# DM1097_HUB.net
KiCad netlist of a schematic drawn in Altium Designer
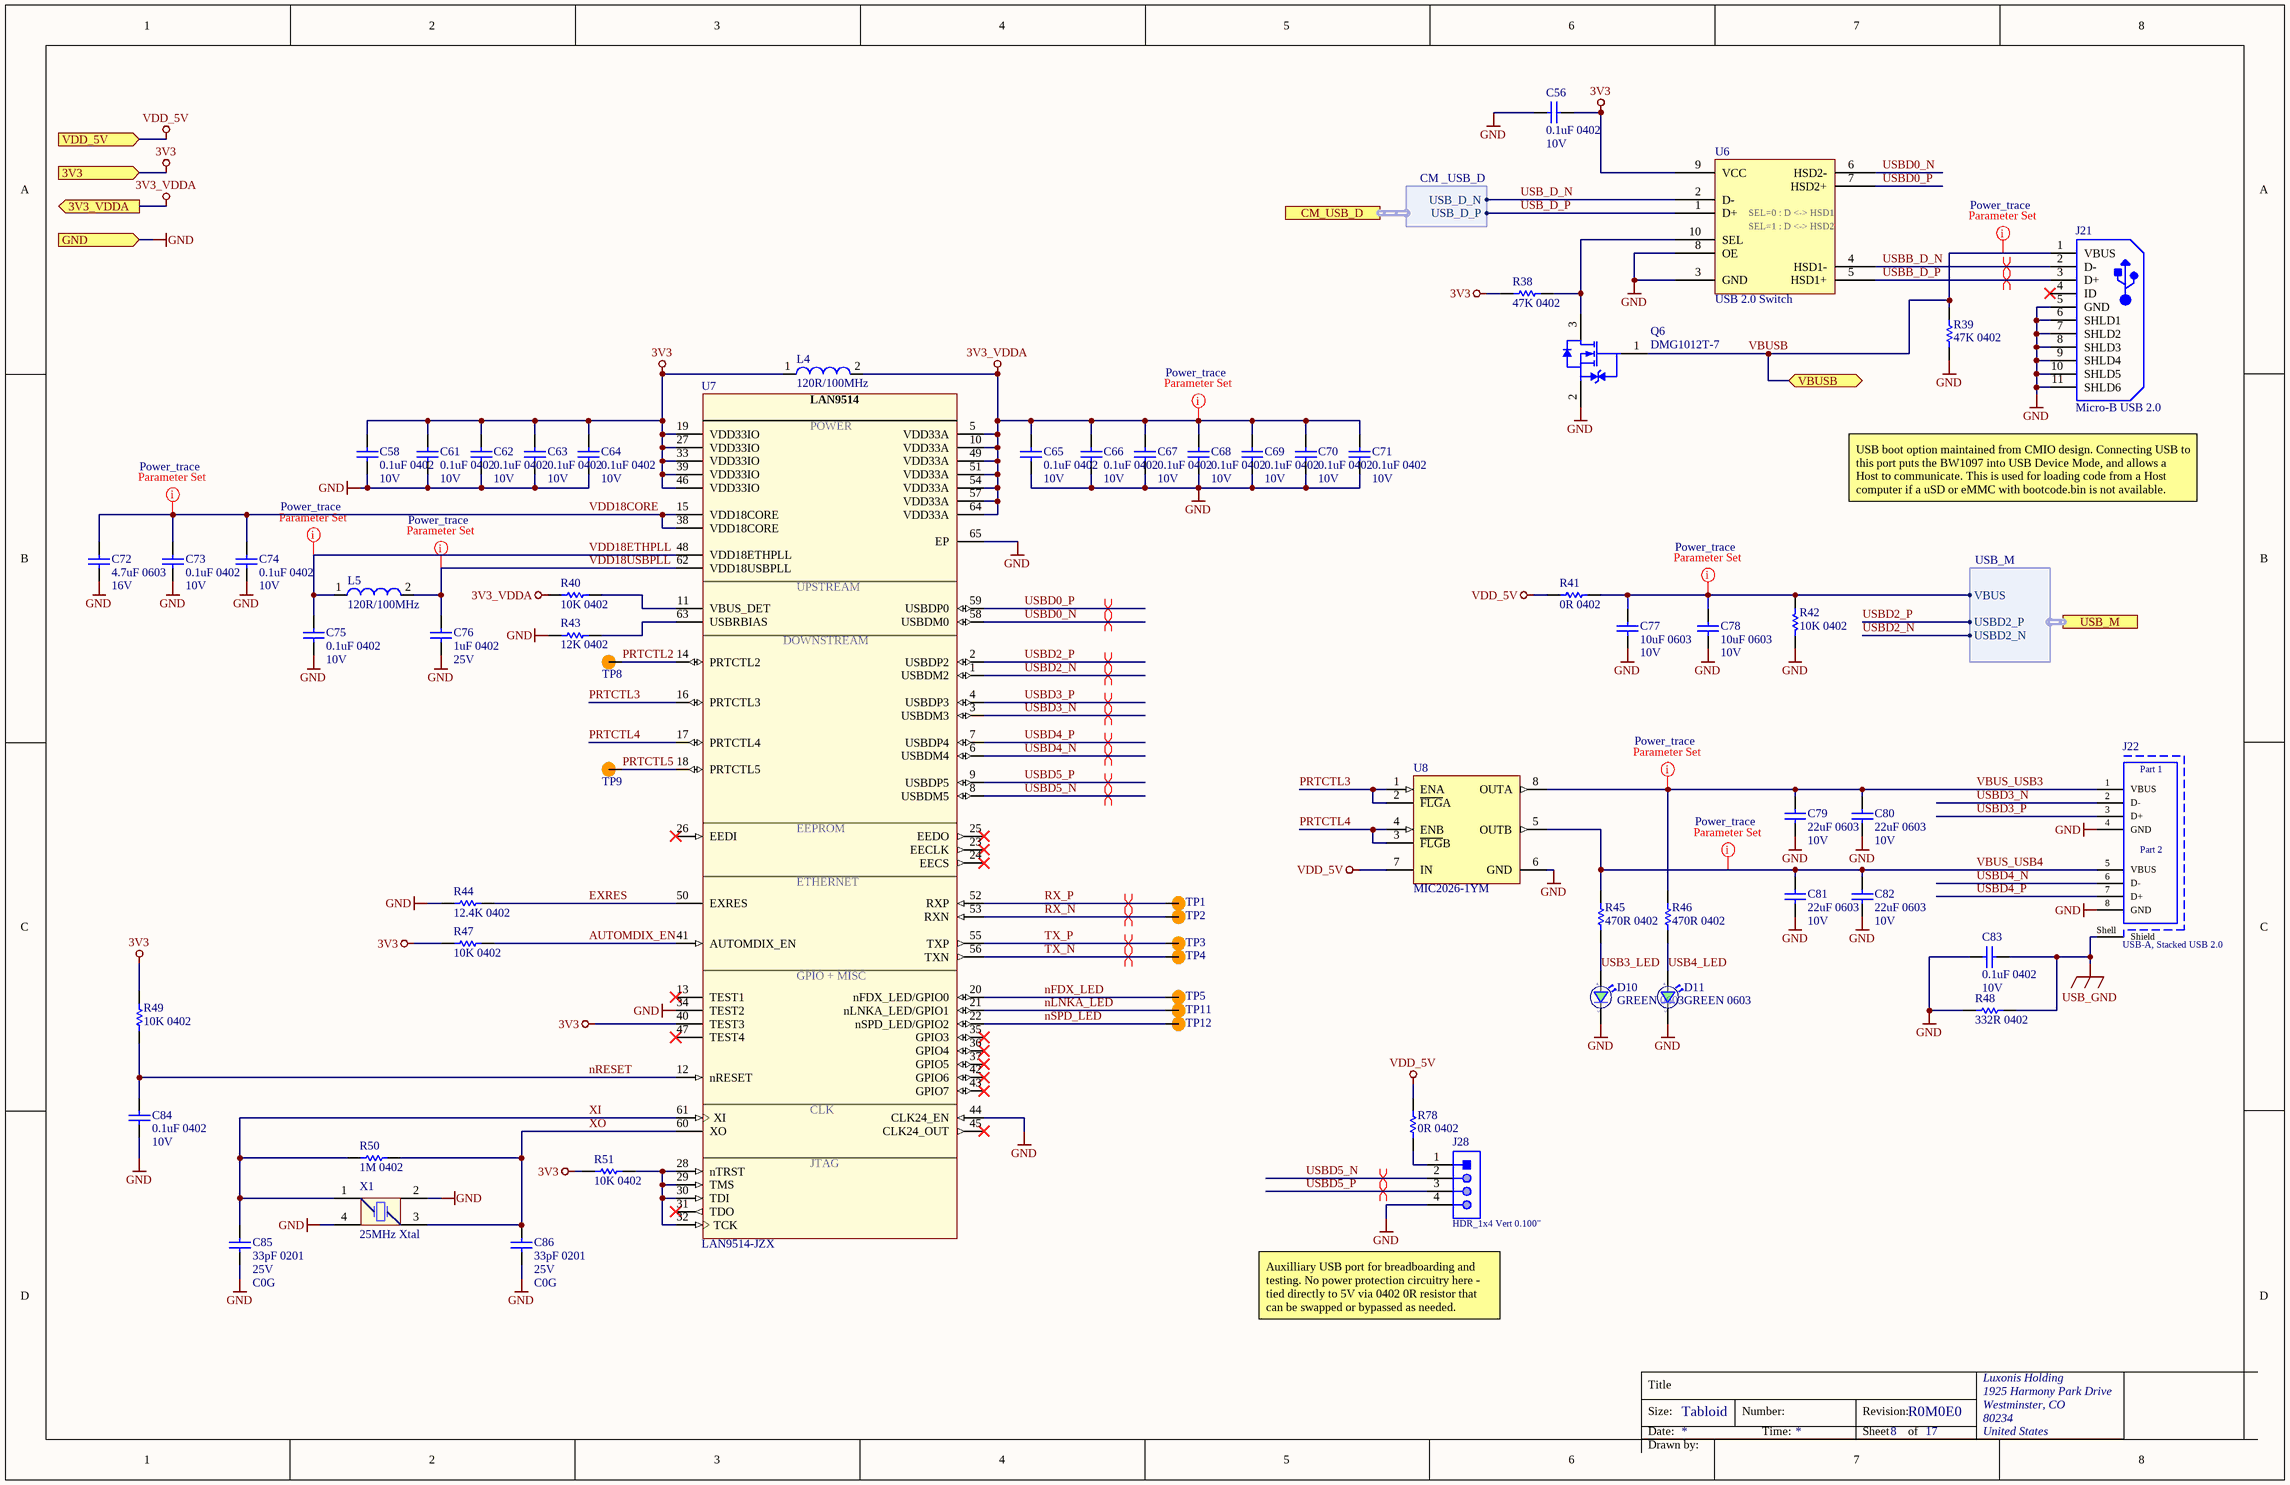
[diagram p0: DM1097_HUB.SchDoc]

(export (version "E")
  (design (tool "Eeschema 10.0.6"))
  (components
    (comp (ref "C56")
      (value "0.1uF 0402")
      (footprint "CAP_Altium_Vault_Generic:CAPC0402(1005)70_N")
      (description "CAP CER 0.1UF 10V X7R 0402 5%")
      (fields (field (name "TOLERANCE") "5%") (field (name "VOLTAGE RATING") "10V"))
      (libsource (lib "LuxonisMaster") (part "GRM155R71A104JA01D"))
    )
    (comp (ref "C58")
      (value "0.1uF 0402")
      (footprint "CAP_Altium_Vault_Generic:CAPC0402(1005)70_N")
      (description "CAP CER 0.1UF 10V X7R 0402 5%")
      (fields (field (name "TOLERANCE") "5%") (field (name "VOLTAGE RATING") "10V"))
      (libsource (lib "LuxonisMaster") (part "GRM155R71A104JA01D"))
    )
    (comp (ref "C61")
      (value "0.1uF 0402")
      (footprint "CAP_Altium_Vault_Generic:CAPC0402(1005)70_N")
      (description "CAP CER 0.1UF 10V X7R 0402 5%")
      (fields (field (name "TOLERANCE") "5%") (field (name "VOLTAGE RATING") "10V"))
      (libsource (lib "LuxonisMaster") (part "GRM155R71A104JA01D"))
    )
    (comp (ref "C62")
      (value "0.1uF 0402")
      (footprint "CAP_Altium_Vault_Generic:CAPC0402(1005)70_N")
      (description "CAP CER 0.1UF 10V X7R 0402 5%")
      (fields (field (name "TOLERANCE") "5%") (field (name "VOLTAGE RATING") "10V"))
      (libsource (lib "LuxonisMaster") (part "GRM155R71A104JA01D"))
    )
    (comp (ref "C63")
      (value "0.1uF 0402")
      (footprint "CAP_Altium_Vault_Generic:CAPC0402(1005)70_N")
      (description "CAP CER 0.1UF 10V X7R 0402 5%")
      (fields (field (name "TOLERANCE") "5%") (field (name "VOLTAGE RATING") "10V"))
      (libsource (lib "LuxonisMaster") (part "GRM155R71A104JA01D"))
    )
    (comp (ref "C64")
      (value "0.1uF 0402")
      (footprint "CAP_Altium_Vault_Generic:CAPC0402(1005)70_N")
      (description "CAP CER 0.1UF 10V X7R 0402 5%")
      (fields (field (name "TOLERANCE") "5%") (field (name "VOLTAGE RATING") "10V"))
      (libsource (lib "LuxonisMaster") (part "GRM155R71A104JA01D"))
    )
    (comp (ref "C65")
      (value "0.1uF 0402")
      (footprint "CAP_Altium_Vault_Generic:CAPC0402(1005)70_N")
      (description "CAP CER 0.1UF 10V X7R 0402 5%")
      (fields (field (name "TOLERANCE") "5%") (field (name "VOLTAGE RATING") "10V"))
      (libsource (lib "LuxonisMaster") (part "GRM155R71A104JA01D"))
    )
    (comp (ref "C66")
      (value "0.1uF 0402")
      (footprint "CAP_Altium_Vault_Generic:CAPC0402(1005)70_N")
      (description "CAP CER 0.1UF 10V X7R 0402 5%")
      (fields (field (name "TOLERANCE") "5%") (field (name "VOLTAGE RATING") "10V"))
      (libsource (lib "LuxonisMaster") (part "GRM155R71A104JA01D"))
    )
    (comp (ref "C67")
      (value "0.1uF 0402")
      (footprint "CAP_Altium_Vault_Generic:CAPC0402(1005)70_N")
      (description "CAP CER 0.1UF 10V X7R 0402 5%")
      (fields (field (name "TOLERANCE") "5%") (field (name "VOLTAGE RATING") "10V"))
      (libsource (lib "LuxonisMaster") (part "GRM155R71A104JA01D"))
    )
    (comp (ref "C68")
      (value "0.1uF 0402")
      (footprint "CAP_Altium_Vault_Generic:CAPC0402(1005)70_N")
      (description "CAP CER 0.1UF 10V X7R 0402 5%")
      (fields (field (name "TOLERANCE") "5%") (field (name "VOLTAGE RATING") "10V"))
      (libsource (lib "LuxonisMaster") (part "GRM155R71A104JA01D"))
    )
    (comp (ref "C69")
      (value "0.1uF 0402")
      (footprint "CAP_Altium_Vault_Generic:CAPC0402(1005)70_N")
      (description "CAP CER 0.1UF 10V X7R 0402 5%")
      (fields (field (name "TOLERANCE") "5%") (field (name "VOLTAGE RATING") "10V"))
      (libsource (lib "LuxonisMaster") (part "GRM155R71A104JA01D"))
    )
    (comp (ref "C70")
      (value "0.1uF 0402")
      (footprint "CAP_Altium_Vault_Generic:CAPC0402(1005)70_N")
      (description "CAP CER 0.1UF 10V X7R 0402 5%")
      (fields (field (name "TOLERANCE") "5%") (field (name "VOLTAGE RATING") "10V"))
      (libsource (lib "LuxonisMaster") (part "GRM155R71A104JA01D"))
    )
    (comp (ref "C71")
      (value "0.1uF 0402")
      (footprint "CAP_Altium_Vault_Generic:CAPC0402(1005)70_N")
      (description "CAP CER 0.1UF 10V X7R 0402 5%")
      (fields (field (name "TOLERANCE") "5%") (field (name "VOLTAGE RATING") "10V"))
      (libsource (lib "LuxonisMaster") (part "GRM155R71A104JA01D"))
    )
    (comp (ref "C72")
      (value "4.7uF 0603")
      (footprint "CAP_Altium_Vault_Generic:CAPC0603(1608)100_N")
      (description "CAP CER 4.7UF 16V X5R 0603 10%")
      (fields (field (name "TOLERANCE") "10%") (field (name "VOLTAGE RATING") "16V"))
      (libsource (lib "LuxonisMaster") (part "GRM188R61C475KAAJD"))
    )
    (comp (ref "C73")
      (value "0.1uF 0402")
      (footprint "CAP_Altium_Vault_Generic:CAPC0402(1005)70_N")
      (description "CAP CER 0.1UF 10V X7R 0402 5%")
      (fields (field (name "TOLERANCE") "5%") (field (name "VOLTAGE RATING") "10V"))
      (libsource (lib "LuxonisMaster") (part "GRM155R71A104JA01D"))
    )
    (comp (ref "C74")
      (value "0.1uF 0402")
      (footprint "CAP_Altium_Vault_Generic:CAPC0402(1005)70_N")
      (description "CAP CER 0.1UF 10V X7R 0402 5%")
      (fields (field (name "TOLERANCE") "5%") (field (name "VOLTAGE RATING") "10V"))
      (libsource (lib "LuxonisMaster") (part "GRM155R71A104JA01D"))
    )
    (comp (ref "C75")
      (value "0.1uF 0402")
      (footprint "CAP_Altium_Vault_Generic:CAPC0402(1005)70_N")
      (description "CAP CER 0.1UF 10V X7R 0402 5%")
      (fields (field (name "TOLERANCE") "5%") (field (name "VOLTAGE RATING") "10V"))
      (libsource (lib "LuxonisMaster") (part "GRM155R71A104JA01D"))
    )
    (comp (ref "C76")
      (value "1uF 0402")
      (footprint "CAP_Altium_Vault_Generic:CAPC0402(1005)70_N")
      (description "CAP CER 1UF 25V X5R 0402 10%")
      (fields
        (field (name "TOLERANCE") "10%")
        (field (name "VOLTAGE") "25V")
        (field (name "VOLTAGE RATING") "25V")
      )
      (libsource (lib "LuxonisMaster") (part "GRM155R61E105KA12D"))
    )
    (comp (ref "C77")
      (value "10uF 0603")
      (footprint "CAP_Altium_Vault_Generic:CAPC0603(1608)100_N")
      (description "CAP CER 10UF 10V X5R 0603 20%")
      (fields (field (name "TOLERANCE") "20%") (field (name "VOLTAGE RATING") "10V"))
      (libsource (lib "LuxonisMaster") (part "GRM188R61A106ME69D"))
    )
    (comp (ref "C78")
      (value "10uF 0603")
      (footprint "CAP_Altium_Vault_Generic:CAPC0603(1608)100_N")
      (description "CAP CER 10UF 10V X5R 0603 20%")
      (fields (field (name "TOLERANCE") "20%") (field (name "VOLTAGE RATING") "10V"))
      (libsource (lib "LuxonisMaster") (part "GRM188R61A106ME69D"))
    )
    (comp (ref "C79")
      (value "22uF 0603")
      (footprint "CAP_Altium_Vault_Generic:CAPC0603(1608)100_N")
      (description "CAP CER 22UF 10V X5R 0603 20%")
      (fields (field (name "TOLERANCE") "20%") (field (name "VOLTAGE RATING") "10V"))
      (libsource (lib "LuxonisMaster") (part "GRM188R61A226ME15D"))
    )
    (comp (ref "C80")
      (value "22uF 0603")
      (footprint "CAP_Altium_Vault_Generic:CAPC0603(1608)100_N")
      (description "CAP CER 22UF 10V X5R 0603 20%")
      (fields (field (name "TOLERANCE") "20%") (field (name "VOLTAGE RATING") "10V"))
      (libsource (lib "LuxonisMaster") (part "GRM188R61A226ME15D"))
    )
    (comp (ref "C81")
      (value "22uF 0603")
      (footprint "CAP_Altium_Vault_Generic:CAPC0603(1608)100_N")
      (description "CAP CER 22UF 10V X5R 0603 20%")
      (fields (field (name "TOLERANCE") "20%") (field (name "VOLTAGE RATING") "10V"))
      (libsource (lib "LuxonisMaster") (part "GRM188R61A226ME15D"))
    )
    (comp (ref "C82")
      (value "22uF 0603")
      (footprint "CAP_Altium_Vault_Generic:CAPC0603(1608)100_N")
      (description "CAP CER 22UF 10V X5R 0603 20%")
      (fields (field (name "TOLERANCE") "20%") (field (name "VOLTAGE RATING") "10V"))
      (libsource (lib "LuxonisMaster") (part "GRM188R61A226ME15D"))
    )
    (comp (ref "C83")
      (value "0.1uF 0402")
      (footprint "CAP_Altium_Vault_Generic:CAPC0402(1005)70_N")
      (description "CAP CER 0.1UF 10V X7R 0402 5%")
      (fields (field (name "TOLERANCE") "5%") (field (name "VOLTAGE RATING") "10V"))
      (libsource (lib "LuxonisMaster") (part "GRM155R71A104JA01D"))
    )
    (comp (ref "C84")
      (value "0.1uF 0402")
      (footprint "CAP_Altium_Vault_Generic:CAPC0402(1005)70_N")
      (description "CAP CER 0.1UF 10V X7R 0402 5%")
      (fields (field (name "TOLERANCE") "5%") (field (name "VOLTAGE RATING") "10V"))
      (libsource (lib "LuxonisMaster") (part "GRM155R71A104JA01D"))
    )
    (comp (ref "C85")
      (value "33pF 0201")
      (footprint "CAP_Altium_Vault_Generic:CAPC0201(0603)33_L")
      (description "CAP CER 33PF 25V C0G/NP0 0201")
      (fields
        (field (name "TOLERANCE") "5%")
        (field (name "VOLTAGE RATING") "25V")
        (field (name "DIELECTRIC") "C0G")
      )
      (libsource (lib "LuxonisMaster") (part "GRM0335C1E330JA01D"))
    )
    (comp (ref "C86")
      (value "33pF 0201")
      (footprint "CAP_Altium_Vault_Generic:CAPC0201(0603)33_L")
      (description "CAP CER 33PF 25V C0G/NP0 0201")
      (fields
        (field (name "TOLERANCE") "5%")
        (field (name "VOLTAGE RATING") "25V")
        (field (name "DIELECTRIC") "C0G")
      )
      (libsource (lib "LuxonisMaster") (part "GRM0335C1E330JA01D"))
    )
    (comp (ref "D10")
      (value "GREEN 0603")
      (footprint "LuxonisMaster:SML_D1xx8W")
      (description "LED GREEN DIFFUSED 0603 SMD Green 572nm LED Indication - Discrete 2.2V 0603 (1608 Metric)")
      (fields (field (name "MANUFACTURER") "Rohm") (field (name "MANUFACTURER PART NUMBER") "SML-D12M8WT86"))
      (libsource (lib "LuxonisMaster") (part "SML-D12M8WT86"))
    )
    (comp (ref "D11")
      (value "GREEN 0603")
      (footprint "LuxonisMaster:SML_D1xx8W")
      (description "LED GREEN DIFFUSED 0603 SMD Green 572nm LED Indication - Discrete 2.2V 0603 (1608 Metric)")
      (fields (field (name "MANUFACTURER") "Rohm") (field (name "MANUFACTURER PART NUMBER") "SML-D12M8WT86"))
      (libsource (lib "LuxonisMaster") (part "SML-D12M8WT86"))
    )
    (comp (ref "J21")
      (value "Micro-B USB 2.0")
      (footprint "LuxonisMaster:10118194-0001LF")
      (libsource (lib "LuxonisMaster") (part "10118194-0001LF"))
    )
    (comp (ref "J22")
      (value "USB-A, Stacked USB 2.0")
      (footprint "LuxonisMaster:61400826021")
      (libsource (lib "LuxonisMaster") (part "61400826021"))
    )
    (comp (ref "J28")
      (value "HDR_1x4 Vert 0.100\"")
      (footprint "LuxonisMaster:61300411121")
      (description "CONN HEADER VERT 4POS 2.54MM  Connector Header Through Hole 4 position 0.100\" (2.54mm)")
      (libsource (lib "LuxonisMaster") (part "61300411121"))
    )
    (comp (ref "L4")
      (value "120R/100MHz")
      (footprint "LuxonisMaster:BLM18PG121SN1D_N")
      (description "FERRITE BEAD 120 OHM 0603 1LN")
      (fields (field (name "TOLERANCE") "25%"))
      (libsource (lib "LuxonisMaster") (part "BLM18PG121SN1D"))
    )
    (comp (ref "L5")
      (value "120R/100MHz")
      (footprint "LuxonisMaster:BLM18PG121SN1D_N")
      (description "FERRITE BEAD 120 OHM 0603 1LN")
      (fields (field (name "TOLERANCE") "25%"))
      (libsource (lib "LuxonisMaster") (part "BLM18PG121SN1D"))
    )
    (comp (ref "Q6")
      (value "DMG1012T-7")
      (footprint "LuxonisMaster:DMG1012T-7")
      (description "MOSFET N-CH 20V 630MA SOT-523")
      (libsource (lib "LuxonisMaster") (part "DMG1012T-7"))
    )
    (comp (ref "R38")
      (value "47K 0402")
      (footprint "RES_Altium_Vault_Generic:RESC0402(1005)_N")
      (description "RES SMD 47K OHM 1% 1/16W 0402")
      (fields (field (name "TOLERANCE") "1%"))
      (libsource (lib "LuxonisMaster") (part "RC0402FR-0747KL"))
    )
    (comp (ref "R39")
      (value "47K 0402")
      (footprint "RES_Altium_Vault_Generic:RESC0402(1005)_N")
      (description "RES SMD 47K OHM 1% 1/16W 0402")
      (fields (field (name "TOLERANCE") "1%"))
      (libsource (lib "LuxonisMaster") (part "RC0402FR-0747KL"))
    )
    (comp (ref "R40")
      (value "10K 0402")
      (footprint "RES_Altium_Vault_Generic:RESC0402(1005)_N")
      (fields (field (name "TOLERANCE") "1%"))
      (libsource (lib "LuxonisMaster") (part "RC0402FR-1310KL"))
    )
    (comp (ref "R41")
      (value "0R 0402")
      (footprint "RES_Altium_Vault_Generic:RESC0402(1005)_N")
      (description "RES SMD 0 OHM JUMPER 1/16W 0402")
      (fields (field (name "TOLERANCE") "5%"))
      (libsource (lib "LuxonisMaster") (part "CRCW04020000Z0ED"))
    )
    (comp (ref "R42")
      (value "10K 0402")
      (footprint "RES_Altium_Vault_Generic:RESC0402(1005)_N")
      (fields (field (name "TOLERANCE") "1%"))
      (libsource (lib "LuxonisMaster") (part "RC0402FR-1310KL"))
    )
    (comp (ref "R43")
      (value "12K 0402")
      (footprint "RES_Altium_Vault_Generic:RESC0402(1005)_N")
      (fields (field (name "TOLERANCE") "1%"))
      (libsource (lib "LuxonisMaster") (part "RC0402FR-0712KL"))
    )
    (comp (ref "R44")
      (value "12.4K 0402")
      (footprint "RES_Altium_Vault_Generic:RESC0402(1005)_N")
      (description "RES SMD 12.4K OHM 1% 1/16W 0402")
      (fields (field (name "TOLERANCE") "1%"))
      (libsource (lib "LuxonisMaster") (part "RC0402FR-0712K4L"))
    )
    (comp (ref "R45")
      (value "470R 0402")
      (footprint "RES_Altium_Vault_Generic:RESC0402(1005)_N")
      (description "RES SMD 470 OHM 1% 1/16W 0402")
      (fields (field (name "TOLERANCE") "1%"))
      (libsource (lib "LuxonisMaster") (part "CRCW0402470RFKED"))
    )
    (comp (ref "R46")
      (value "470R 0402")
      (footprint "RES_Altium_Vault_Generic:RESC0402(1005)_N")
      (description "RES SMD 470 OHM 1% 1/16W 0402")
      (fields (field (name "TOLERANCE") "1%"))
      (libsource (lib "LuxonisMaster") (part "CRCW0402470RFKED"))
    )
    (comp (ref "R47")
      (value "10K 0402")
      (footprint "RES_Altium_Vault_Generic:RESC0402(1005)_N")
      (fields (field (name "TOLERANCE") "1%"))
      (libsource (lib "LuxonisMaster") (part "RC0402FR-1310KL"))
    )
    (comp (ref "R48")
      (value "332R 0402")
      (footprint "RES_Altium_Vault_Generic:RESC0402(1005)_N")
      (description "RES SMD 332 OHM 1% 1/16W 0402")
      (fields (field (name "TOLERANCE") "1%"))
      (libsource (lib "LuxonisMaster") (part "RC0402FR-07332RL"))
    )
    (comp (ref "R49")
      (value "10K 0402")
      (footprint "RES_Altium_Vault_Generic:RESC0402(1005)_N")
      (fields (field (name "TOLERANCE") "1%"))
      (libsource (lib "LuxonisMaster") (part "RC0402FR-1310KL"))
    )
    (comp (ref "R50")
      (value "1M 0402")
      (footprint "RES_Altium_Vault_Generic:RESC0402(1005)_N")
      (description "RES SMD 1M OHM 1% 1/16W 0402")
      (fields (field (name "TOLERANCE") "1%"))
      (libsource (lib "LuxonisMaster") (part "RC0402FR-071ML"))
    )
    (comp (ref "R51")
      (value "10K 0402")
      (footprint "RES_Altium_Vault_Generic:RESC0402(1005)_N")
      (fields (field (name "TOLERANCE") "1%"))
      (libsource (lib "LuxonisMaster") (part "RC0402FR-1310KL"))
    )
    (comp (ref "R78")
      (value "0R 0402")
      (footprint "RES_Altium_Vault_Generic:RESC0402(1005)_N")
      (description "RES SMD 0 OHM JUMPER 1/16W 0402")
      (fields (field (name "TOLERANCE") "5%"))
      (libsource (lib "LuxonisMaster") (part "CRCW04020000Z0ED"))
    )
    (comp (ref "TP1")
      (value "TP100_200_NS")
      (footprint "LuxonisMaster:TP100_200_NS")
      (libsource (lib "LuxonisMaster") (part "TEST_POINT"))
    )
    (comp (ref "TP2")
      (value "TP100_200_NS")
      (footprint "LuxonisMaster:TP100_200_NS")
      (libsource (lib "LuxonisMaster") (part "TEST_POINT"))
    )
    (comp (ref "TP3")
      (value "TP100_200_NS")
      (footprint "LuxonisMaster:TP100_200_NS")
      (libsource (lib "LuxonisMaster") (part "TEST_POINT"))
    )
    (comp (ref "TP4")
      (value "TP100_200_NS")
      (footprint "LuxonisMaster:TP100_200_NS")
      (libsource (lib "LuxonisMaster") (part "TEST_POINT"))
    )
    (comp (ref "TP5")
      (value "TP100_200_NS")
      (footprint "LuxonisMaster:TP100_200_NS")
      (libsource (lib "LuxonisMaster") (part "TEST_POINT"))
    )
    (comp (ref "TP8")
      (value "TP100_200_NS")
      (footprint "LuxonisMaster:TP100_200_NS")
      (libsource (lib "LuxonisMaster") (part "TEST_POINT"))
    )
    (comp (ref "TP9")
      (value "TP100_200_NS")
      (footprint "LuxonisMaster:TP100_200_NS")
      (libsource (lib "LuxonisMaster") (part "TEST_POINT"))
    )
    (comp (ref "TP11")
      (value "TP100_200_NS")
      (footprint "LuxonisMaster:TP100_200_NS")
      (libsource (lib "LuxonisMaster") (part "TEST_POINT"))
    )
    (comp (ref "TP12")
      (value "TP100_200_NS")
      (footprint "LuxonisMaster:TP100_200_NS")
      (libsource (lib "LuxonisMaster") (part "TEST_POINT"))
    )
    (comp (ref "U6")
      (value "USB 2.0 Switch")
      (footprint "LuxonisMaster:FSUSB42UMX")
      (description "IC USB SWITCH DPDT 10UMLP")
      (libsource (lib "LuxonisMaster") (part "FSUSB42UMX"))
    )
    (comp (ref "U7")
      (value "LAN9514-JZX")
      (footprint "LuxonisMaster:LAN951x-JZX")
      (libsource (lib "LuxonisMaster") (part "LAN9514-JZX"))
    )
    (comp (ref "U8")
      (value "MIC2026-1YM")
      (footprint "LuxonisMaster:MIC2026-1YM")
      (description "IC PW DIST SW DUAL 8SOIC Power Switch/Driver 1:2 N-Channel 500mA 8-SOIC")
      (fields (field (name "MANUFACTURER") "Micrel"))
      (libsource (lib "LuxonisMaster") (part "MIC2026-1YM"))
    )
    (comp (ref "X1")
      (value "25MHz Xtal")
      (footprint "LuxonisMaster:8Z-25.000MAAJ-T")
      (description "CRYSTAL 25.0000MHZ 18PF SMD")
      (fields (field (name "TOLERANCE") "30ppm"))
      (libsource (lib "LuxonisMaster") (part "8Z-25.000MAAJ-T"))
    )
  )
  (nets
    (net (code "4") (name "/AUTOMDIX_EN") (class "Default")
      (node (ref "R47") (pin "2") (pinfunction "2_2") (pintype "passive"))
      (node (ref "U7") (pin "41") (pinfunction "AUTOMDIX_EN_41") (pintype "input"))
    )
    (net (code "5") (name "/EXRES") (class "Default")
      (node (ref "R44") (pin "2") (pinfunction "2_2") (pintype "passive"))
      (node (ref "U7") (pin "50") (pinfunction "EXRES_50") (pintype "passive"))
    )
    (net (code "6") (name "/PRTCTL2") (class "Default")
      (node (ref "TP8") (pin "1") (pintype "passive"))
      (node (ref "U7") (pin "14") (pinfunction "PRTCTL2_14") (pintype "bidirectional"))
    )
    (net (code "7") (name "/PRTCTL3") (class "Default")
      (node (ref "U7") (pin "16") (pinfunction "PRTCTL3_16") (pintype "bidirectional"))
      (node (ref "U8") (pin "1") (pinfunction "ENA_1") (pintype "input"))
      (node (ref "U8") (pin "2") (pinfunction "~{FLG}A_2") (pintype "open_collector"))
    )
    (net (code "8") (name "/PRTCTL4") (class "Default")
      (node (ref "U7") (pin "17") (pinfunction "PRTCTL4_17") (pintype "bidirectional"))
      (node (ref "U8") (pin "3") (pinfunction "~{FLG}B_3") (pintype "open_collector"))
      (node (ref "U8") (pin "4") (pinfunction "ENB_4") (pintype "input"))
    )
    (net (code "9") (name "/PRTCTL5") (class "Default")
      (node (ref "TP9") (pin "1") (pintype "passive"))
      (node (ref "U7") (pin "18") (pinfunction "PRTCTL5_18") (pintype "bidirectional"))
    )
    (net (code "10") (name "/RX_N") (class "Default")
      (node (ref "TP2") (pin "1") (pintype "passive"))
      (node (ref "U7") (pin "53") (pinfunction "RXN_53") (pintype "input"))
    )
    (net (code "11") (name "/RX_P") (class "Default")
      (node (ref "TP1") (pin "1") (pintype "passive"))
      (node (ref "U7") (pin "52") (pinfunction "RXP_52") (pintype "input"))
    )
    (net (code "12") (name "/TX_N") (class "Default")
      (node (ref "TP4") (pin "1") (pintype "passive"))
      (node (ref "U7") (pin "56") (pinfunction "TXN_56") (pintype "output"))
    )
    (net (code "13") (name "/TX_P") (class "Default")
      (node (ref "TP3") (pin "1") (pintype "passive"))
      (node (ref "U7") (pin "55") (pinfunction "TXP_55") (pintype "output"))
    )
    (net (code "14") (name "/USB3_LED") (class "Default")
      (node (ref "D10") (pin "2") (pinfunction "A_2") (pintype "passive"))
      (node (ref "R45") (pin "1") (pinfunction "1_1") (pintype "passive"))
    )
    (net (code "15") (name "/USB4_LED") (class "Default")
      (node (ref "D11") (pin "2") (pinfunction "A_2") (pintype "passive"))
      (node (ref "R46") (pin "1") (pinfunction "1_1") (pintype "passive"))
    )
    (net (code "16") (name "/USBB_D_N") (class "Default")
      (node (ref "J21") (pin "2") (pinfunction "D-_2") (pintype "passive"))
      (node (ref "U6") (pin "4") (pinfunction "HSD1-_4") (pintype "passive"))
    )
    (net (code "17") (name "/USBB_D_P") (class "Default")
      (node (ref "J21") (pin "3") (pinfunction "D+_3") (pintype "passive"))
      (node (ref "U6") (pin "5") (pinfunction "HSD1+_5") (pintype "passive"))
    )
    (net (code "18") (name "/USBD0_N") (class "Default")
      (node (ref "U6") (pin "6") (pinfunction "HSD2-_6") (pintype "passive"))
      (node (ref "U7") (pin "58") (pinfunction "USBDM0_58") (pintype "bidirectional"))
    )
    (net (code "19") (name "/USBD0_P") (class "Default")
      (node (ref "U6") (pin "7") (pinfunction "HSD2+_7") (pintype "passive"))
      (node (ref "U7") (pin "59") (pinfunction "USBDP0_59") (pintype "bidirectional"))
    )
    (net (code "20") (name "/USBD2_N") (class "Default")
      (node (ref "U7") (pin "1") (pinfunction "USBDM2_1") (pintype "bidirectional"))
    )
    (net (code "21") (name "/USBD2_P") (class "Default")
      (node (ref "U7") (pin "2") (pinfunction "USBDP2_2") (pintype "bidirectional"))
    )
    (net (code "22") (name "/USBD3_N") (class "Default")
      (node (ref "J22") (pin "2") (pinfunction "D-_2") (pintype "passive"))
      (node (ref "U7") (pin "3") (pinfunction "USBDM3_3") (pintype "bidirectional"))
    )
    (net (code "23") (name "/USBD3_P") (class "Default")
      (node (ref "J22") (pin "3") (pinfunction "D+_3") (pintype "passive"))
      (node (ref "U7") (pin "4") (pinfunction "USBDP3_4") (pintype "bidirectional"))
    )
    (net (code "24") (name "/USBD4_N") (class "Default")
      (node (ref "J22") (pin "6") (pinfunction "D-_6") (pintype "passive"))
      (node (ref "U7") (pin "6") (pinfunction "USBDM4_6") (pintype "bidirectional"))
    )
    (net (code "25") (name "/USBD4_P") (class "Default")
      (node (ref "J22") (pin "7") (pinfunction "D+_7") (pintype "passive"))
      (node (ref "U7") (pin "7") (pinfunction "USBDP4_7") (pintype "bidirectional"))
    )
    (net (code "26") (name "/USBD5_N") (class "Default")
      (node (ref "J28") (pin "2") (pinfunction "2_2") (pintype "passive"))
      (node (ref "U7") (pin "8") (pinfunction "USBDM5_8") (pintype "bidirectional"))
    )
    (net (code "27") (name "/USBD5_P") (class "Default")
      (node (ref "J28") (pin "3") (pinfunction "3_3") (pintype "passive"))
      (node (ref "U7") (pin "9") (pinfunction "USBDP5_9") (pintype "bidirectional"))
    )
    (net (code "28") (name "/USB_D_N") (class "Default")
      (node (ref "U6") (pin "2") (pinfunction "D-_2") (pintype "passive"))
    )
    (net (code "29") (name "/USB_D_P") (class "Default")
      (node (ref "U6") (pin "1") (pinfunction "D+_1") (pintype "passive"))
    )
    (net (code "30") (name "/VBUSB") (class "Default")
      (node (ref "J21") (pin "1") (pinfunction "VBUS_1") (pintype "passive"))
      (node (ref "Q6") (pin "1") (pinfunction "1_1") (pintype "passive"))
      (node (ref "R39") (pin "2") (pinfunction "2_2") (pintype "passive"))
    )
    (net (code "31") (name "/VBUS_USB3") (class "Default")
      (node (ref "C79") (pin "1") (pinfunction "1_1") (pintype "passive"))
      (node (ref "C80") (pin "1") (pinfunction "1_1") (pintype "passive"))
      (node (ref "J22") (pin "1") (pinfunction "VBUS_1") (pintype "passive"))
      (node (ref "R46") (pin "2") (pinfunction "2_2") (pintype "passive"))
      (node (ref "U8") (pin "8") (pinfunction "OUTA_8") (pintype "output"))
    )
    (net (code "32") (name "/VBUS_USB4") (class "Default")
      (node (ref "C81") (pin "1") (pinfunction "1_1") (pintype "passive"))
      (node (ref "C82") (pin "1") (pinfunction "1_1") (pintype "passive"))
      (node (ref "J22") (pin "5") (pinfunction "VBUS_5") (pintype "passive"))
      (node (ref "R45") (pin "2") (pinfunction "2_2") (pintype "passive"))
      (node (ref "U8") (pin "5") (pinfunction "OUTB_5") (pintype "output"))
    )
    (net (code "33") (name "/VDD18CORE") (class "Default")
      (node (ref "C72") (pin "2") (pinfunction "2_2") (pintype "passive"))
      (node (ref "C73") (pin "2") (pinfunction "2_2") (pintype "passive"))
      (node (ref "C74") (pin "2") (pinfunction "2_2") (pintype "passive"))
      (node (ref "U7") (pin "15") (pinfunction "VDD18CORE_15") (pintype "power_in"))
      (node (ref "U7") (pin "38") (pinfunction "VDD18CORE_38") (pintype "power_in"))
    )
    (net (code "34") (name "/VDD18ETHPLL") (class "Default")
      (node (ref "C75") (pin "2") (pinfunction "2_2") (pintype "passive"))
      (node (ref "L5") (pin "1") (pinfunction "1_1") (pintype "passive"))
      (node (ref "U7") (pin "48") (pinfunction "VDD18ETHPLL_48") (pintype "power_in"))
    )
    (net (code "35") (name "/VDD18USBPLL") (class "Default")
      (node (ref "C76") (pin "2") (pinfunction "2_2") (pintype "passive"))
      (node (ref "L5") (pin "2") (pinfunction "2_2") (pintype "passive"))
      (node (ref "U7") (pin "62") (pinfunction "VDD18USBPLL_62") (pintype "power_in"))
    )
    (net (code "36") (name "/XI") (class "Default")
      (node (ref "C85") (pin "2") (pinfunction "2_2") (pintype "passive"))
      (node (ref "R50") (pin "1") (pinfunction "1_1") (pintype "passive"))
      (node (ref "U7") (pin "61") (pinfunction "XI_61") (pintype "input"))
      (node (ref "X1") (pin "1") (pinfunction "OSC1_1") (pintype "passive"))
    )
    (net (code "37") (name "/XO") (class "Default")
      (node (ref "C86") (pin "2") (pinfunction "2_2") (pintype "passive"))
      (node (ref "R50") (pin "2") (pinfunction "2_2") (pintype "passive"))
      (node (ref "U7") (pin "60") (pinfunction "XO_60") (pintype "passive"))
      (node (ref "X1") (pin "3") (pinfunction "OSC3_3") (pintype "passive"))
    )
    (net (code "38") (name "/nFDX_LED") (class "Default")
      (node (ref "TP5") (pin "1") (pintype "passive"))
      (node (ref "U7") (pin "20") (pinfunction "nFDX_LED/GPIO0_20") (pintype "bidirectional"))
    )
    (net (code "39") (name "/nLNKA_LED") (class "Default")
      (node (ref "TP11") (pin "1") (pintype "passive"))
      (node (ref "U7") (pin "21") (pinfunction "nLNKA_LED/GPIO1_21") (pintype "bidirectional"))
    )
    (net (code "40") (name "/nRESET") (class "Default")
      (node (ref "C84") (pin "2") (pinfunction "2_2") (pintype "passive"))
      (node (ref "R49") (pin "2") (pinfunction "2_2") (pintype "passive"))
      (node (ref "U7") (pin "12") (pinfunction "nRESET_12") (pintype "input"))
    )
    (net (code "41") (name "/nSPD_LED") (class "Default")
      (node (ref "TP12") (pin "1") (pintype "passive"))
      (node (ref "U7") (pin "22") (pinfunction "nSPD_LED/GPIO2_22") (pintype "bidirectional"))
    )
    (net (code "44") (name "3V3") (class "Default")
      (node (ref "C56") (pin "1") (pinfunction "1_1") (pintype "passive"))
      (node (ref "C58") (pin "2") (pinfunction "2_2") (pintype "passive"))
      (node (ref "C61") (pin "2") (pinfunction "2_2") (pintype "passive"))
      (node (ref "C62") (pin "2") (pinfunction "2_2") (pintype "passive"))
      (node (ref "C63") (pin "2") (pinfunction "2_2") (pintype "passive"))
      (node (ref "C64") (pin "2") (pinfunction "2_2") (pintype "passive"))
      (node (ref "L4") (pin "1") (pinfunction "1_1") (pintype "passive"))
      (node (ref "R38") (pin "1") (pinfunction "1_1") (pintype "passive"))
      (node (ref "R47") (pin "1") (pinfunction "1_1") (pintype "passive"))
      (node (ref "R49") (pin "1") (pinfunction "1_1") (pintype "passive"))
      (node (ref "R51") (pin "1") (pinfunction "1_1") (pintype "passive"))
      (node (ref "U6") (pin "9") (pinfunction "VCC_9") (pintype "passive"))
      (node (ref "U7") (pin "19") (pinfunction "VDD33IO_19") (pintype "power_in"))
      (node (ref "U7") (pin "27") (pinfunction "VDD33IO_27") (pintype "power_in"))
      (node (ref "U7") (pin "33") (pinfunction "VDD33IO_33") (pintype "power_in"))
      (node (ref "U7") (pin "39") (pinfunction "VDD33IO_39") (pintype "power_in"))
      (node (ref "U7") (pin "40") (pinfunction "TEST3_40") (pintype "passive"))
      (node (ref "U7") (pin "46") (pinfunction "VDD33IO_46") (pintype "power_in"))
    )
    (net (code "45") (name "3V3_VDDA") (class "Default")
      (node (ref "C65") (pin "2") (pinfunction "2_2") (pintype "passive"))
      (node (ref "C66") (pin "2") (pinfunction "2_2") (pintype "passive"))
      (node (ref "C67") (pin "2") (pinfunction "2_2") (pintype "passive"))
      (node (ref "C68") (pin "2") (pinfunction "2_2") (pintype "passive"))
      (node (ref "C69") (pin "2") (pinfunction "2_2") (pintype "passive"))
      (node (ref "C70") (pin "2") (pinfunction "2_2") (pintype "passive"))
      (node (ref "C71") (pin "2") (pinfunction "2_2") (pintype "passive"))
      (node (ref "L4") (pin "2") (pinfunction "2_2") (pintype "passive"))
      (node (ref "R40") (pin "1") (pinfunction "1_1") (pintype "passive"))
      (node (ref "U7") (pin "10") (pinfunction "VDD33A_10") (pintype "power_in"))
      (node (ref "U7") (pin "49") (pinfunction "VDD33A_49") (pintype "power_in"))
      (node (ref "U7") (pin "5") (pinfunction "VDD33A_5") (pintype "power_in"))
      (node (ref "U7") (pin "51") (pinfunction "VDD33A_51") (pintype "power_in"))
      (node (ref "U7") (pin "54") (pinfunction "VDD33A_54") (pintype "power_in"))
      (node (ref "U7") (pin "57") (pinfunction "VDD33A_57") (pintype "power_in"))
      (node (ref "U7") (pin "64") (pinfunction "VDD33A_64") (pintype "power_in"))
    )
    (net (code "46") (name "GND") (class "Default")
      (node (ref "C56") (pin "2") (pinfunction "2_2") (pintype "passive"))
      (node (ref "C58") (pin "1") (pinfunction "1_1") (pintype "passive"))
      (node (ref "C61") (pin "1") (pinfunction "1_1") (pintype "passive"))
      (node (ref "C62") (pin "1") (pinfunction "1_1") (pintype "passive"))
      (node (ref "C63") (pin "1") (pinfunction "1_1") (pintype "passive"))
      (node (ref "C64") (pin "1") (pinfunction "1_1") (pintype "passive"))
      (node (ref "C65") (pin "1") (pinfunction "1_1") (pintype "passive"))
      (node (ref "C66") (pin "1") (pinfunction "1_1") (pintype "passive"))
      (node (ref "C67") (pin "1") (pinfunction "1_1") (pintype "passive"))
      (node (ref "C68") (pin "1") (pinfunction "1_1") (pintype "passive"))
      (node (ref "C69") (pin "1") (pinfunction "1_1") (pintype "passive"))
      (node (ref "C70") (pin "1") (pinfunction "1_1") (pintype "passive"))
      (node (ref "C71") (pin "1") (pinfunction "1_1") (pintype "passive"))
      (node (ref "C72") (pin "1") (pinfunction "1_1") (pintype "passive"))
      (node (ref "C73") (pin "1") (pinfunction "1_1") (pintype "passive"))
      (node (ref "C74") (pin "1") (pinfunction "1_1") (pintype "passive"))
      (node (ref "C75") (pin "1") (pinfunction "1_1") (pintype "passive"))
      (node (ref "C76") (pin "1") (pinfunction "1_1") (pintype "passive"))
      (node (ref "C77") (pin "1") (pinfunction "1_1") (pintype "passive"))
      (node (ref "C78") (pin "1") (pinfunction "1_1") (pintype "passive"))
      (node (ref "C79") (pin "2") (pinfunction "2_2") (pintype "passive"))
      (node (ref "C80") (pin "2") (pinfunction "2_2") (pintype "passive"))
      (node (ref "C81") (pin "2") (pinfunction "2_2") (pintype "passive"))
      (node (ref "C82") (pin "2") (pinfunction "2_2") (pintype "passive"))
      (node (ref "C83") (pin "1") (pinfunction "1_1") (pintype "passive"))
      (node (ref "C84") (pin "1") (pinfunction "1_1") (pintype "passive"))
      (node (ref "C85") (pin "1") (pinfunction "1_1") (pintype "passive"))
      (node (ref "C86") (pin "1") (pinfunction "1_1") (pintype "passive"))
      (node (ref "D10") (pin "1") (pinfunction "C_1") (pintype "passive"))
      (node (ref "D11") (pin "1") (pinfunction "C_1") (pintype "passive"))
      (node (ref "J21") (pin "10") (pinfunction "SHLD5_10") (pintype "passive"))
      (node (ref "J21") (pin "11") (pinfunction "SHLD6_11") (pintype "passive"))
      (node (ref "J21") (pin "5") (pinfunction "GND_5") (pintype "passive"))
      (node (ref "J21") (pin "6") (pinfunction "SHLD1_6") (pintype "passive"))
      (node (ref "J21") (pin "7") (pinfunction "SHLD2_7") (pintype "passive"))
      (node (ref "J21") (pin "8") (pinfunction "SHLD3_8") (pintype "passive"))
      (node (ref "J21") (pin "9") (pinfunction "SHLD4_9") (pintype "passive"))
      (node (ref "J22") (pin "4") (pinfunction "GND_4") (pintype "passive"))
      (node (ref "J22") (pin "8") (pinfunction "GND_8") (pintype "passive"))
      (node (ref "J28") (pin "4") (pinfunction "4_4") (pintype "passive"))
      (node (ref "Q6") (pin "2") (pinfunction "2_2") (pintype "passive"))
      (node (ref "R39") (pin "1") (pinfunction "1_1") (pintype "passive"))
      (node (ref "R42") (pin "1") (pinfunction "1_1") (pintype "passive"))
      (node (ref "R43") (pin "1") (pinfunction "1_1") (pintype "passive"))
      (node (ref "R44") (pin "1") (pinfunction "1_1") (pintype "passive"))
      (node (ref "R48") (pin "1") (pinfunction "1_1") (pintype "passive"))
      (node (ref "U6") (pin "3") (pinfunction "GND_3") (pintype "passive"))
      (node (ref "U6") (pin "8") (pinfunction "OE_8") (pintype "passive"))
      (node (ref "U7") (pin "34") (pinfunction "TEST2_34") (pintype "passive"))
      (node (ref "U7") (pin "44") (pinfunction "CLK24_EN_44") (pintype "input"))
      (node (ref "U7") (pin "65") (pinfunction "EP_65") (pintype "power_in"))
      (node (ref "U8") (pin "6") (pinfunction "GND_6") (pintype "power_in"))
      (node (ref "X1") (pin "2") (pinfunction "2_2") (pintype "passive"))
      (node (ref "X1") (pin "4") (pinfunction "4_4") (pintype "passive"))
    )
    (net (code "47") (name "Net-(C77-Pad2)") (class "Default")
      (node (ref "C77") (pin "2") (pinfunction "2_2") (pintype "passive"))
      (node (ref "C78") (pin "2") (pinfunction "2_2") (pintype "passive"))
      (node (ref "R41") (pin "1") (pinfunction "1_1") (pintype "passive"))
      (node (ref "R42") (pin "2") (pinfunction "2_2") (pintype "passive"))
    )
    (net (code "48") (name "Net-(J28-Pad1)") (class "Default")
      (node (ref "J28") (pin "1") (pinfunction "1_1") (pintype "passive"))
      (node (ref "R78") (pin "1") (pinfunction "1_1") (pintype "passive"))
    )
    (net (code "49") (name "Net-(U6-SEL)") (class "Default")
      (node (ref "Q6") (pin "3") (pinfunction "3_3") (pintype "passive"))
      (node (ref "R38") (pin "2") (pinfunction "2_2") (pintype "passive"))
      (node (ref "U6") (pin "10") (pinfunction "SEL_10") (pintype "passive"))
    )
    (net (code "50") (name "Net-(U7-TCK)") (class "Default")
      (node (ref "R51") (pin "2") (pinfunction "2_2") (pintype "passive"))
      (node (ref "U7") (pin "28") (pinfunction "nTRST_28") (pintype "input"))
      (node (ref "U7") (pin "29") (pinfunction "TMS_29") (pintype "input"))
      (node (ref "U7") (pin "30") (pinfunction "TDI_30") (pintype "input"))
      (node (ref "U7") (pin "32") (pinfunction "TCK_32") (pintype "input"))
    )
    (net (code "51") (name "Net-(U7-USBRBIAS)") (class "Default")
      (node (ref "R43") (pin "2") (pinfunction "2_2") (pintype "passive"))
      (node (ref "U7") (pin "63") (pinfunction "USBRBIAS_63") (pintype "passive"))
    )
    (net (code "52") (name "Net-(U7-VBUS_DET)") (class "Default")
      (node (ref "R40") (pin "2") (pinfunction "2_2") (pintype "passive"))
      (node (ref "U7") (pin "11") (pinfunction "VBUS_DET_11") (pintype "power_in"))
    )
    (net (code "53") (name "USB_GND") (class "Default")
      (node (ref "C83") (pin "2") (pinfunction "2_2") (pintype "passive"))
      (node (ref "J22") (pin "Shell") (pinfunction "Shield_Shell") (pintype "passive"))
      (node (ref "R48") (pin "2") (pinfunction "2_2") (pintype "passive"))
    )
    (net (code "54") (name "VDD_5V") (class "Default")
      (node (ref "R41") (pin "2") (pinfunction "2_2") (pintype "passive"))
      (node (ref "R78") (pin "2") (pinfunction "2_2") (pintype "passive"))
      (node (ref "U8") (pin "7") (pinfunction "IN_7") (pintype "power_in"))
    )
    (net (code "55") (name "unconnected-(J21-ID-Pad4)") (class "Default")
      (node (ref "J21") (pin "4") (pinfunction "ID_4") (pintype "passive+no_connect"))
    )
    (net (code "56") (name "unconnected-(U7-CLK24_OUT-Pad45)") (class "Default")
      (node (ref "U7") (pin "45") (pinfunction "CLK24_OUT_45") (pintype "output+no_connect"))
    )
    (net (code "57") (name "unconnected-(U7-EECLK-Pad23)") (class "Default")
      (node (ref "U7") (pin "23") (pinfunction "EECLK_23") (pintype "output+no_connect"))
    )
    (net (code "58") (name "unconnected-(U7-EECS-Pad24)") (class "Default")
      (node (ref "U7") (pin "24") (pinfunction "EECS_24") (pintype "output+no_connect"))
    )
    (net (code "59") (name "unconnected-(U7-EEDI-Pad26)") (class "Default")
      (node (ref "U7") (pin "26") (pinfunction "EEDI_26") (pintype "input+no_connect"))
    )
    (net (code "60") (name "unconnected-(U7-EEDO-Pad25)") (class "Default")
      (node (ref "U7") (pin "25") (pinfunction "EEDO_25") (pintype "output+no_connect"))
    )
    (net (code "61") (name "unconnected-(U7-GPIO3-Pad35)") (class "Default")
      (node (ref "U7") (pin "35") (pinfunction "GPIO3_35") (pintype "bidirectional+no_connect"))
    )
    (net (code "62") (name "unconnected-(U7-GPIO4-Pad36)") (class "Default")
      (node (ref "U7") (pin "36") (pinfunction "GPIO4_36") (pintype "bidirectional+no_connect"))
    )
    (net (code "63") (name "unconnected-(U7-GPIO5-Pad37)") (class "Default")
      (node (ref "U7") (pin "37") (pinfunction "GPIO5_37") (pintype "bidirectional+no_connect"))
    )
    (net (code "64") (name "unconnected-(U7-GPIO6-Pad42)") (class "Default")
      (node (ref "U7") (pin "42") (pinfunction "GPIO6_42") (pintype "bidirectional+no_connect"))
    )
    (net (code "65") (name "unconnected-(U7-GPIO7-Pad43)") (class "Default")
      (node (ref "U7") (pin "43") (pinfunction "GPIO7_43") (pintype "bidirectional+no_connect"))
    )
    (net (code "66") (name "unconnected-(U7-TDO-Pad31)") (class "Default")
      (node (ref "U7") (pin "31") (pinfunction "TDO_31") (pintype "output+no_connect"))
    )
    (net (code "67") (name "unconnected-(U7-TEST1-Pad13)") (class "Default")
      (node (ref "U7") (pin "13") (pinfunction "TEST1_13") (pintype "passive+no_connect"))
    )
    (net (code "68") (name "unconnected-(U7-TEST4-Pad47)") (class "Default")
      (node (ref "U7") (pin "47") (pinfunction "TEST4_47") (pintype "passive+no_connect"))
    )
  )
)
